# Photo_Board.net
KiCad netlist of a schematic drawn in Altium Designer
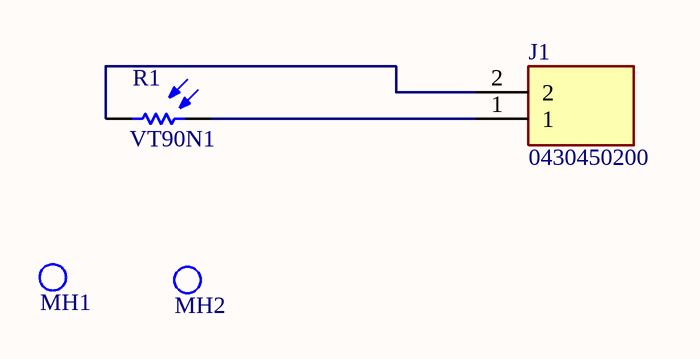
[diagram p0: Photo Board.SchDoc]

(export (version "E")
  (design (tool "Eeschema 10.0.6"))
  (components
    (comp (ref "J1")
      (value "0430450200")
      (footprint "SamacSys:43045-0200")
      (description "Connector")
      (libsource (lib "SamacSys") (part "0430450200"))
    )
    (comp (ref "MH1")
      (value "Mounting Hole")
      (footprint "MOUNT-HOLE")
      (description "#4 Screw, 0.116in Diameter")
      (libsource (lib "SOARSchematics") (part "Mounting Hole"))
    )
    (comp (ref "MH2")
      (value "Mounting Hole")
      (footprint "MOUNT-HOLE")
      (description "#4 Screw, 0.116in Diameter")
      (libsource (lib "SOARSchematics") (part "Mounting Hole"))
    )
    (comp (ref "R1")
      (value "VT90N1")
      (footprint "EXCE-VT90N1")
      (description "Photoconductive Resistor, 200 kOhm, 100 V, 80 mW, -40 to 75 degC, 2-Pin THD, RoHS")
      (fields (field (name "MANUFACTURER") "Excelitas Technology"))
      (libsource (lib "Altium Content Vault") (part "PHOTO-RES-2"))
    )
  )
  (nets
    (net (code "1") (name "Net-(J1-Pad1)") (class "Default")
      (node (ref "J1") (pin "1") (pinfunction "1_1") (pintype "passive"))
      (node (ref "R1") (pin "2") (pinfunction "2_2") (pintype "passive"))
    )
    (net (code "2") (name "Net-(J1-Pad2)") (class "Default")
      (node (ref "J1") (pin "2") (pinfunction "2_2") (pintype "passive"))
      (node (ref "R1") (pin "1") (pinfunction "1_1") (pintype "passive"))
    )
  )
)
